# M8_AUX_CONN.net
KiCad netlist of a schematic drawn in Altium Designer
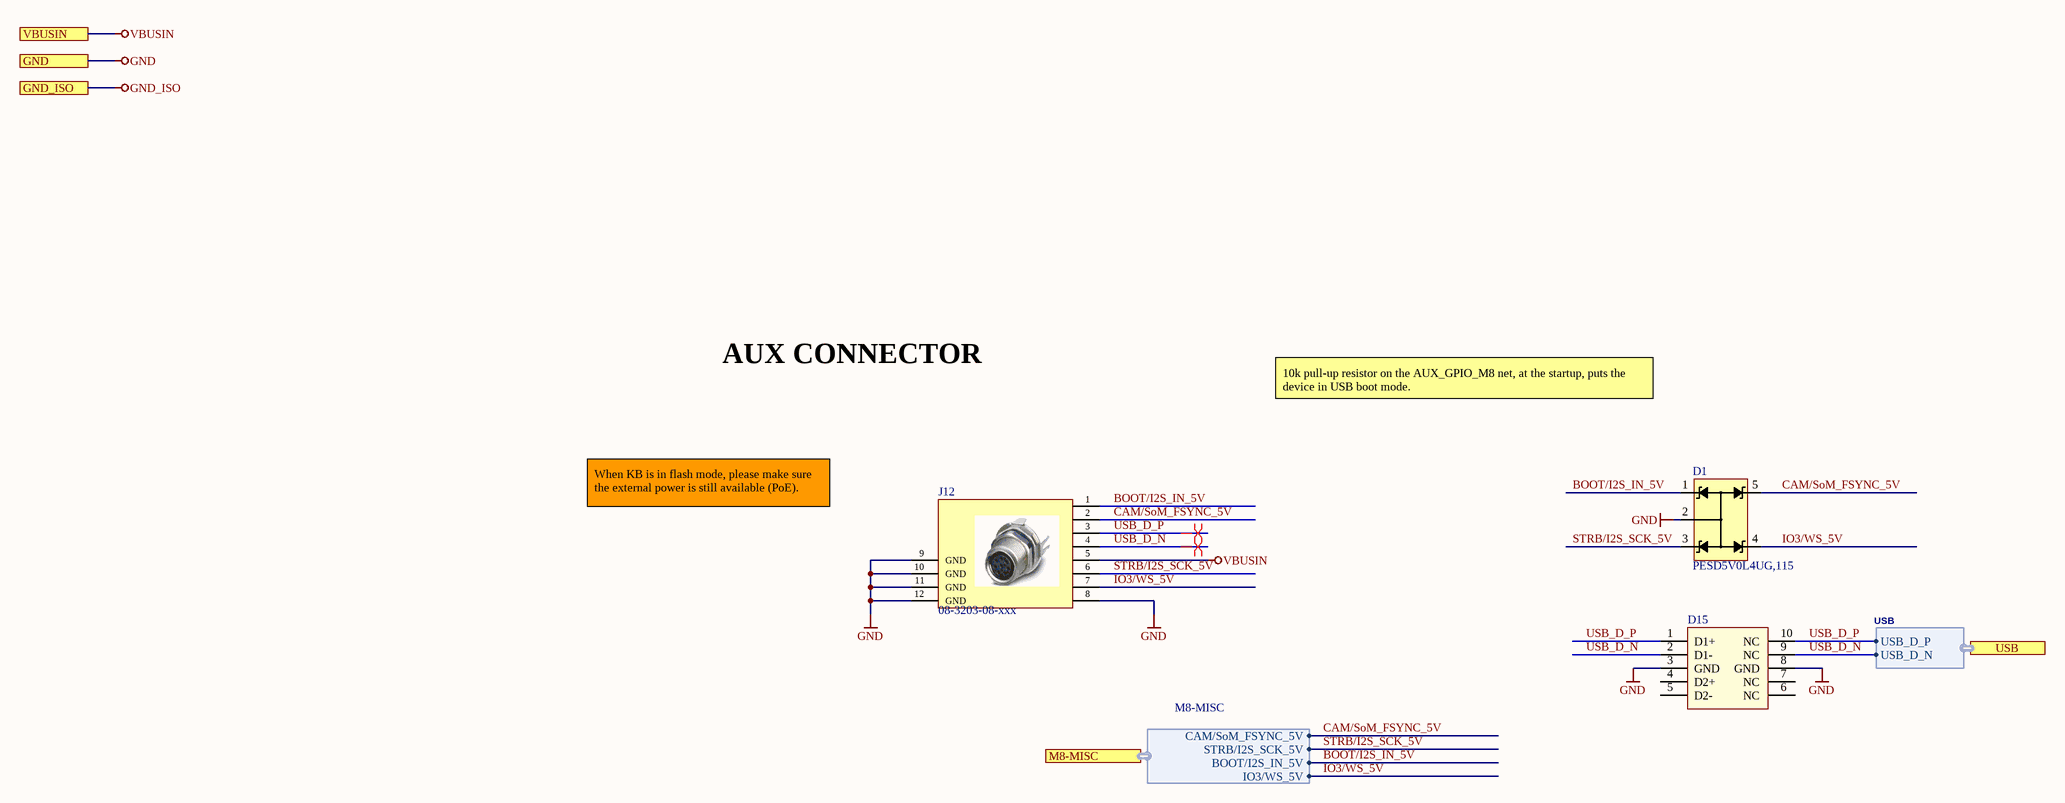
[diagram p0: M8_AUX_CONN.SchDoc]

(export (version "E")
  (design (tool "Eeschema 10.0.6"))
  (components
    (comp (ref "D1")
      (value "PESD5V0L4UG,115")
      (footprint "PESD3V3L4UG,115")
      (description "TVS DIODE 5V 12V 5TSSOP")
      (libsource (lib "Luxonis LLC") (part "PESD5V0L4UG,115"))
    )
    (comp (ref "D15")
      (value "TPD4EUSB30DQAR")
      (footprint "TPD4EUSB30DQAR")
      (description "TVS DIODE 5.5V 8V 10SON 8V Clamp 1A (8/20µs) Ipp Tvs Diode Surface Mount 10-USON (2.5x1)")
      (libsource (lib "Luxonis LLC") (part "TPD4EUSB30DQAR"))
    )
    (comp (ref "J12")
      (value "08-3203-08-xxx")
      (footprint "08-3203-08-XXX")
      (description "M8 Circular Connector")
      (libsource (lib "Luxonis LLC") (part "08-3203-08-xxx"))
    )
  )
  (nets
    (net (code "3") (name "/BOOT{slash}I2S_IN_5V") (class "Default")
      (node (ref "D1") (pin "1") (pinfunction "1_1") (pintype "passive"))
      (node (ref "J12") (pin "1") (pinfunction "1_1") (pintype "passive"))
    )
    (net (code "4") (name "/CAM{slash}SoM_FSYNC_5V") (class "Default")
      (node (ref "D1") (pin "5") (pinfunction "5_5") (pintype "passive"))
      (node (ref "J12") (pin "2") (pinfunction "2_2") (pintype "passive"))
    )
    (net (code "5") (name "/IO3{slash}WS_5V") (class "Default")
      (node (ref "D1") (pin "4") (pinfunction "4_4") (pintype "passive"))
      (node (ref "J12") (pin "7") (pinfunction "7_7") (pintype "passive"))
    )
    (net (code "6") (name "/STRB{slash}I2S_SCK_5V") (class "Default")
      (node (ref "D1") (pin "3") (pinfunction "3_3") (pintype "passive"))
      (node (ref "J12") (pin "6") (pinfunction "6_6") (pintype "passive"))
    )
    (net (code "7") (name "/USB_D_N") (class "Default")
      (node (ref "D15") (pin "2") (pinfunction "D1-_2") (pintype "passive"))
      (node (ref "D15") (pin "9") (pinfunction "NC_9") (pintype "passive"))
      (node (ref "J12") (pin "4") (pinfunction "4_4") (pintype "passive"))
    )
    (net (code "8") (name "/USB_D_P") (class "Default")
      (node (ref "D15") (pin "1") (pinfunction "D1+_1") (pintype "passive"))
      (node (ref "D15") (pin "10") (pinfunction "NC_10") (pintype "passive"))
      (node (ref "J12") (pin "3") (pinfunction "3_3") (pintype "passive"))
    )
    (net (code "11") (name "GND") (class "Default")
      (node (ref "D1") (pin "2") (pinfunction "2_2") (pintype "passive"))
      (node (ref "D15") (pin "3") (pinfunction "GND_3") (pintype "passive"))
      (node (ref "D15") (pin "8") (pinfunction "GND_8") (pintype "passive"))
      (node (ref "J12") (pin "10") (pinfunction "GND_10") (pintype "passive"))
      (node (ref "J12") (pin "11") (pinfunction "GND_11") (pintype "passive"))
      (node (ref "J12") (pin "12") (pinfunction "GND_12") (pintype "passive"))
      (node (ref "J12") (pin "8") (pinfunction "8_8") (pintype "passive"))
      (node (ref "J12") (pin "9") (pinfunction "GND_9") (pintype "passive"))
    )
    (net (code "13") (name "VBUSIN") (class "Default")
      (node (ref "J12") (pin "5") (pinfunction "5_5") (pintype "passive"))
    )
    (net (code "14") (name "unconnected-(D15-D2+-Pad4)") (class "Default")
      (node (ref "D15") (pin "4") (pinfunction "D2+_4") (pintype "passive"))
    )
    (net (code "15") (name "unconnected-(D15-D2--Pad5)") (class "Default")
      (node (ref "D15") (pin "5") (pinfunction "D2-_5") (pintype "passive"))
    )
    (net (code "16") (name "unconnected-(D15-NC-Pad6)") (class "Default")
      (node (ref "D15") (pin "6") (pinfunction "NC_6") (pintype "passive"))
    )
    (net (code "17") (name "unconnected-(D15-NC-Pad7)") (class "Default")
      (node (ref "D15") (pin "7") (pinfunction "NC_7") (pintype "passive"))
    )
  )
)
